# Controler_2_25.net
KiCad netlist of a schematic drawn in EAGLE
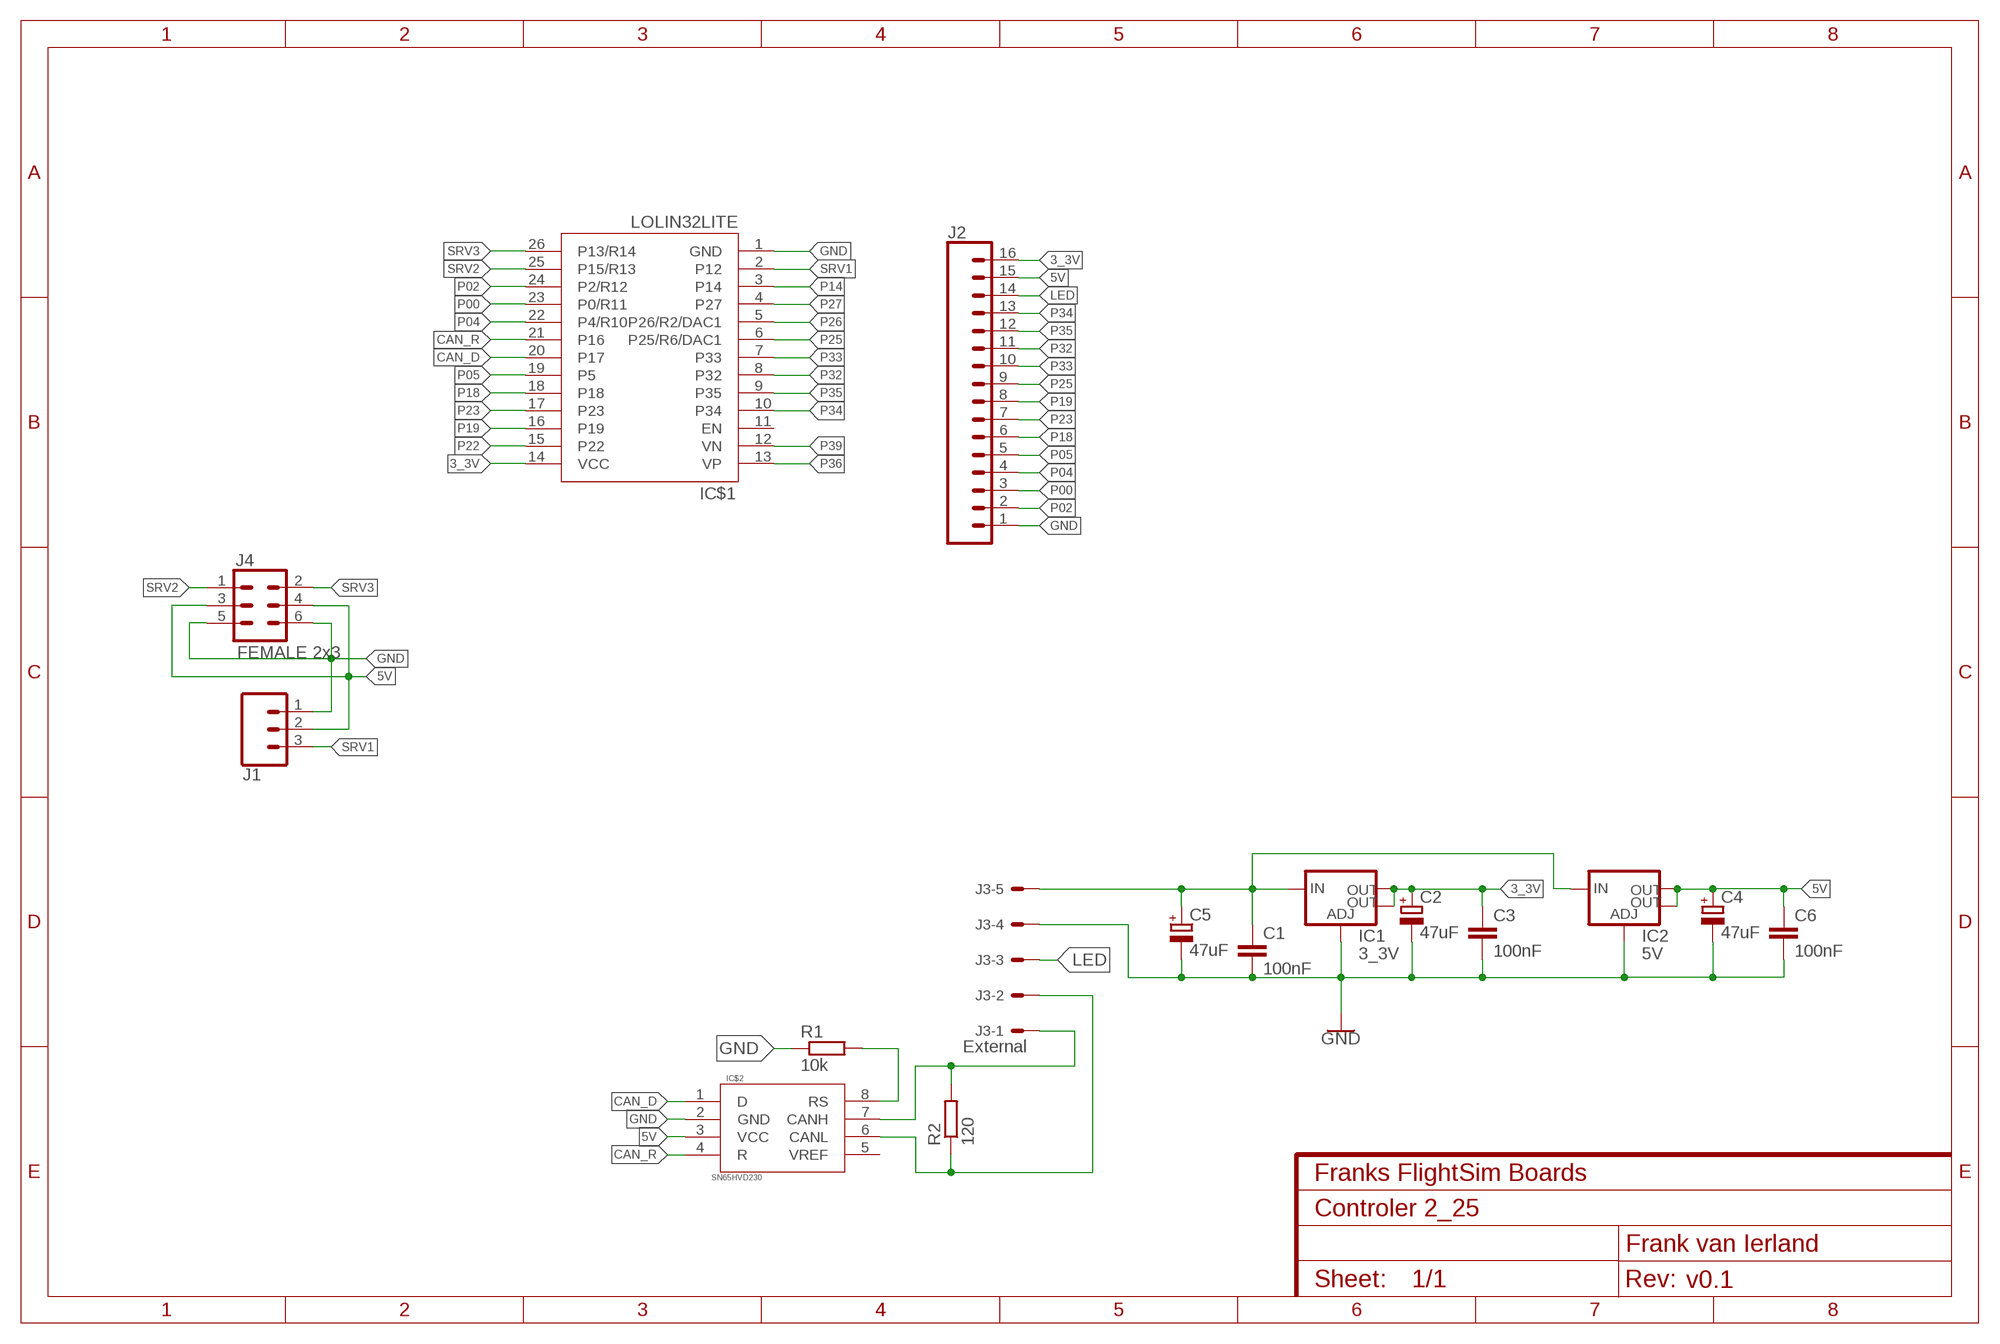
[diagram p0: schematic, sheet 1]

(export (version "E")
  (design (tool "Eeschema 10.0.6"))
  (components
    (comp (ref "C1")
      (value "100nF")
      (footprint "eagle-import:C1206")
      (libsource (lib "eagle-import") (part "C-EUC1206"))
    )
    (comp (ref "C2")
      (value "47uF")
      (footprint "eagle-import:CT3528")
      (libsource (lib "eagle-import") (part "CPOL-EUCT3528"))
    )
    (comp (ref "C3")
      (value "100nF")
      (footprint "eagle-import:C1206")
      (libsource (lib "eagle-import") (part "C-EUC1206"))
    )
    (comp (ref "C4")
      (value "47uF")
      (footprint "eagle-import:CT3528")
      (libsource (lib "eagle-import") (part "CPOL-EUCT3528"))
    )
    (comp (ref "C5")
      (value "47uF")
      (footprint "eagle-import:153CLV-0605")
      (libsource (lib "eagle-import") (part "CPOL-EU153CLV-0605"))
    )
    (comp (ref "C6")
      (value "100nF")
      (footprint "eagle-import:C1206")
      (libsource (lib "eagle-import") (part "C-EUC1206"))
    )
    (comp (ref "IC$1")
      (value "LOLIN32LITE")
      (footprint "eagle-import:LOLIN32LITE")
      (libsource (lib "eagle-import") (part "LOLIN32LITE"))
    )
    (comp (ref "IC$2")
      (value "SN65HVD230")
      (footprint "eagle-import:SO08")
      (libsource (lib "eagle-import") (part "SN65HVD230"))
    )
    (comp (ref "IC1")
      (value "3_3V")
      (footprint "eagle-import:SOT223")
      (libsource (lib "eagle-import") (part "V_REG_LM1117SOT223"))
    )
    (comp (ref "IC2")
      (value "5V")
      (footprint "eagle-import:SOT223")
      (libsource (lib "eagle-import") (part "V_REG_LM1117SOT223"))
    )
    (comp (ref "J1")
      (value "CONN_03")
      (footprint "eagle-import:1X03")
      (libsource (lib "eagle-import") (part "CONN_03"))
    )
    (comp (ref "J2")
      (value "CONN_16")
      (footprint "eagle-import:1X16")
      (libsource (lib "eagle-import") (part "CONN_16"))
    )
    (comp (ref "J3")
      (value "External")
      (footprint "eagle-import:6410-05")
      (fields (field (name "MF") "MOLEX"))
      (libsource (lib "eagle-import") (part "22-?-0527-2051"))
    )
    (comp (ref "J4")
      (value "FEMALE 2x3")
      (footprint "eagle-import:2X3")
      (libsource (lib "eagle-import") (part "CONN_03X2FEMALE"))
    )
    (comp (ref "R1")
      (value "10k")
      (footprint "eagle-import:M1206")
      (libsource (lib "eagle-import") (part "R-EU_M1206"))
    )
    (comp (ref "R2")
      (value "120")
      (footprint "eagle-import:R1210")
      (libsource (lib "eagle-import") (part "R-EU_R1210"))
    )
  )
  (nets
    (net (code "1") (name "3_3V") (class "Default")
      (node (ref "C2") (pin "-") (pinfunction "+_-") (pintype "passive"))
      (node (ref "C3") (pin "1") (pinfunction "1_1") (pintype "passive"))
      (node (ref "IC$1") (pin "14") (pinfunction "VCC_14") (pintype "power_in"))
      (node (ref "IC1") (pin "2") (pinfunction "OUT_2") (pintype "output"))
      (node (ref "IC1") (pin "4") (pinfunction "OUT_4") (pintype "output"))
      (node (ref "J2") (pin "16") (pinfunction "16_16") (pintype "passive"))
    )
    (net (code "2") (name "5V") (class "Default")
      (node (ref "C4") (pin "-") (pinfunction "+_-") (pintype "passive"))
      (node (ref "C6") (pin "1") (pinfunction "1_1") (pintype "passive"))
      (node (ref "IC$2") (pin "3") (pinfunction "VCC_3") (pintype "bidirectional"))
      (node (ref "IC2") (pin "2") (pinfunction "OUT_2") (pintype "output"))
      (node (ref "IC2") (pin "4") (pinfunction "OUT_4") (pintype "output"))
      (node (ref "J1") (pin "2") (pinfunction "2_2") (pintype "passive"))
      (node (ref "J2") (pin "15") (pinfunction "15_15") (pintype "passive"))
      (node (ref "J4") (pin "3") (pinfunction "3_3") (pintype "bidirectional"))
      (node (ref "J4") (pin "4") (pinfunction "4_4") (pintype "bidirectional"))
    )
    (net (code "3") (name "CAN_D") (class "Default")
      (node (ref "IC$1") (pin "20") (pinfunction "P17_20") (pintype "bidirectional"))
      (node (ref "IC$2") (pin "1") (pinfunction "D_1") (pintype "bidirectional"))
    )
    (net (code "4") (name "CAN_R") (class "Default")
      (node (ref "IC$1") (pin "21") (pinfunction "P16_21") (pintype "bidirectional"))
      (node (ref "IC$2") (pin "4") (pinfunction "R_4") (pintype "bidirectional"))
    )
    (net (code "5") (name "GND") (class "Default")
      (node (ref "C1") (pin "2") (pinfunction "2_2") (pintype "passive"))
      (node (ref "C2") (pin "+") (pinfunction "-_+") (pintype "passive"))
      (node (ref "C3") (pin "2") (pinfunction "2_2") (pintype "passive"))
      (node (ref "C4") (pin "+") (pinfunction "-_+") (pintype "passive"))
      (node (ref "C5") (pin "-") (pinfunction "-_-") (pintype "passive"))
      (node (ref "C6") (pin "2") (pinfunction "2_2") (pintype "passive"))
      (node (ref "IC$1") (pin "1") (pinfunction "GND_1") (pintype "power_in"))
      (node (ref "IC$2") (pin "2") (pinfunction "GND_2") (pintype "bidirectional"))
      (node (ref "IC1") (pin "1") (pinfunction "ADJ_1") (pintype "input"))
      (node (ref "IC2") (pin "1") (pinfunction "ADJ_1") (pintype "input"))
      (node (ref "J1") (pin "1") (pinfunction "1_1") (pintype "passive"))
      (node (ref "J2") (pin "1") (pinfunction "1_1") (pintype "passive"))
      (node (ref "J3") (pin "4") (pinfunction "S_4") (pintype "passive"))
      (node (ref "J4") (pin "5") (pinfunction "5_5") (pintype "bidirectional"))
      (node (ref "J4") (pin "6") (pinfunction "6_6") (pintype "bidirectional"))
      (node (ref "R1") (pin "1") (pinfunction "1_1") (pintype "passive"))
    )
    (net (code "6") (name "LED") (class "Default")
      (node (ref "J2") (pin "14") (pinfunction "14_14") (pintype "passive"))
      (node (ref "J3") (pin "3") (pinfunction "S_3") (pintype "passive"))
    )
    (net (code "7") (name "Net-(IC$2-CANH)") (class "Default")
      (node (ref "IC$2") (pin "7") (pinfunction "CANH_7") (pintype "bidirectional"))
      (node (ref "J3") (pin "1") (pinfunction "S_1") (pintype "passive"))
      (node (ref "R2") (pin "2") (pinfunction "2_2") (pintype "passive"))
    )
    (net (code "8") (name "Net-(IC$2-CANL)") (class "Default")
      (node (ref "IC$2") (pin "6") (pinfunction "CANL_6") (pintype "bidirectional"))
      (node (ref "J3") (pin "2") (pinfunction "S_2") (pintype "passive"))
      (node (ref "R2") (pin "1") (pinfunction "1_1") (pintype "passive"))
    )
    (net (code "9") (name "Net-(IC$2-RS)") (class "Default")
      (node (ref "IC$2") (pin "8") (pinfunction "RS_8") (pintype "bidirectional"))
      (node (ref "R1") (pin "2") (pinfunction "2_2") (pintype "passive"))
    )
    (net (code "10") (name "Net-(IC1-IN)") (class "Default")
      (node (ref "C1") (pin "1") (pinfunction "1_1") (pintype "passive"))
      (node (ref "C5") (pin "+") (pinfunction "+_+") (pintype "passive"))
      (node (ref "IC1") (pin "3") (pinfunction "IN_3") (pintype "input"))
      (node (ref "IC2") (pin "3") (pinfunction "IN_3") (pintype "input"))
      (node (ref "J3") (pin "5") (pinfunction "S_5") (pintype "passive"))
    )
    (net (code "11") (name "P00") (class "Default")
      (node (ref "IC$1") (pin "23") (pinfunction "P0/R11_23") (pintype "bidirectional"))
      (node (ref "J2") (pin "3") (pinfunction "3_3") (pintype "passive"))
    )
    (net (code "12") (name "P02") (class "Default")
      (node (ref "IC$1") (pin "24") (pinfunction "P2/R12_24") (pintype "bidirectional"))
      (node (ref "J2") (pin "2") (pinfunction "2_2") (pintype "passive"))
    )
    (net (code "13") (name "P04") (class "Default")
      (node (ref "IC$1") (pin "22") (pinfunction "P4/R10_22") (pintype "bidirectional"))
      (node (ref "J2") (pin "4") (pinfunction "4_4") (pintype "passive"))
    )
    (net (code "14") (name "P05") (class "Default")
      (node (ref "IC$1") (pin "19") (pinfunction "P5_19") (pintype "bidirectional"))
      (node (ref "J2") (pin "5") (pinfunction "5_5") (pintype "passive"))
    )
    (net (code "15") (name "P14") (class "Default")
      (node (ref "IC$1") (pin "3") (pinfunction "P14_3") (pintype "bidirectional"))
    )
    (net (code "16") (name "P18") (class "Default")
      (node (ref "IC$1") (pin "18") (pinfunction "P18_18") (pintype "bidirectional"))
      (node (ref "J2") (pin "6") (pinfunction "6_6") (pintype "passive"))
    )
    (net (code "17") (name "P19") (class "Default")
      (node (ref "IC$1") (pin "16") (pinfunction "P19_16") (pintype "bidirectional"))
      (node (ref "J2") (pin "8") (pinfunction "8_8") (pintype "passive"))
    )
    (net (code "18") (name "P22") (class "Default")
      (node (ref "IC$1") (pin "15") (pinfunction "P22_15") (pintype "bidirectional"))
    )
    (net (code "19") (name "P23") (class "Default")
      (node (ref "IC$1") (pin "17") (pinfunction "P23_17") (pintype "bidirectional"))
      (node (ref "J2") (pin "7") (pinfunction "7_7") (pintype "passive"))
    )
    (net (code "20") (name "P25") (class "Default")
      (node (ref "IC$1") (pin "6") (pinfunction "P25/R6/DAC1_6") (pintype "bidirectional"))
      (node (ref "J2") (pin "9") (pinfunction "9_9") (pintype "passive"))
    )
    (net (code "21") (name "P26") (class "Default")
      (node (ref "IC$1") (pin "5") (pinfunction "P26/R2/DAC1_5") (pintype "bidirectional"))
    )
    (net (code "22") (name "P27") (class "Default")
      (node (ref "IC$1") (pin "4") (pinfunction "P27_4") (pintype "bidirectional"))
    )
    (net (code "23") (name "P32") (class "Default")
      (node (ref "IC$1") (pin "8") (pinfunction "P32_8") (pintype "bidirectional"))
      (node (ref "J2") (pin "11") (pinfunction "11_11") (pintype "passive"))
    )
    (net (code "24") (name "P33") (class "Default")
      (node (ref "IC$1") (pin "7") (pinfunction "P33_7") (pintype "bidirectional"))
      (node (ref "J2") (pin "10") (pinfunction "10_10") (pintype "passive"))
    )
    (net (code "25") (name "P34") (class "Default")
      (node (ref "IC$1") (pin "10") (pinfunction "P34_10") (pintype "bidirectional"))
      (node (ref "J2") (pin "13") (pinfunction "13_13") (pintype "passive"))
    )
    (net (code "26") (name "P35") (class "Default")
      (node (ref "IC$1") (pin "9") (pinfunction "P35_9") (pintype "bidirectional"))
      (node (ref "J2") (pin "12") (pinfunction "12_12") (pintype "passive"))
    )
    (net (code "27") (name "P36") (class "Default")
      (node (ref "IC$1") (pin "13") (pinfunction "VP_13") (pintype "bidirectional"))
    )
    (net (code "28") (name "P39") (class "Default")
      (node (ref "IC$1") (pin "12") (pinfunction "VN_12") (pintype "bidirectional"))
    )
    (net (code "29") (name "SRV1") (class "Default")
      (node (ref "IC$1") (pin "2") (pinfunction "P12_2") (pintype "bidirectional"))
      (node (ref "J1") (pin "3") (pinfunction "3_3") (pintype "passive"))
    )
    (net (code "30") (name "SRV2") (class "Default")
      (node (ref "IC$1") (pin "25") (pinfunction "P15/R13_25") (pintype "bidirectional"))
      (node (ref "J4") (pin "1") (pinfunction "1_1") (pintype "bidirectional"))
    )
    (net (code "31") (name "SRV3") (class "Default")
      (node (ref "IC$1") (pin "26") (pinfunction "P13/R14_26") (pintype "bidirectional"))
      (node (ref "J4") (pin "2") (pinfunction "2_2") (pintype "bidirectional"))
    )
    (net (code "32") (name "unconnected-(IC$1-EN-Pad11)") (class "Default")
      (node (ref "IC$1") (pin "11") (pinfunction "EN_11") (pintype "bidirectional"))
    )
    (net (code "33") (name "unconnected-(IC$2-VREF-Pad5)") (class "Default")
      (node (ref "IC$2") (pin "5") (pinfunction "VREF_5") (pintype "bidirectional"))
    )
  )
)
